# 3_3VTo5V.net
KiCad netlist of a schematic drawn in Altium Designer
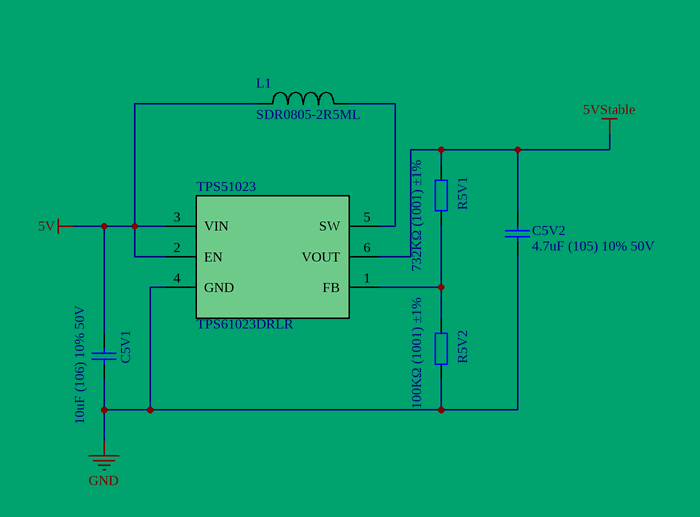
[diagram p0: 3.3VTo5V.SchDoc]

(export (version "E")
  (design (tool "Eeschema 10.0.6"))
  (components
    (comp (ref "C5V1")
      (value "10uF (106) 10% 50V")
      (footprint "1206_C")
      (description "贴片电容")
      (libsource (lib "AD封装2018.9.19Miscellaneous Devices LC") (part "1206 10uF (106) 10% 50V"))
    )
    (comp (ref "C5V2")
      (value "4.7uF (105) 10% 50V")
      (footprint "1206_C")
      (description "贴片电容")
      (libsource (lib "AD封装2018.9.19Miscellaneous Devices LC") (part "1206 1uF (105) 10% 50V"))
    )
    (comp (ref "L1")
      (value "SDR0805-2R5ML")
      (footprint "SDR0805")
      (description "Imported")
      (libsource (lib "ExportLIBCompile") (part "SDR0805-2R5ML"))
    )
    (comp (ref "R5V1")
      (value "732KΩ (1001) ±1%")
      (footprint "1206_R")
      (description "贴片电阻")
      (libsource (lib "AD封装2018.9.19Miscellaneous Devices LC") (part "1206 1KΩ (1001) 1%"))
    )
    (comp (ref "R5V2")
      (value "100KΩ (1001) ±1%")
      (footprint "1206_R")
      (description "贴片电阻")
      (libsource (lib "AD封装2018.9.19Miscellaneous Devices LC") (part "1206 1KΩ (1001) 1%"))
    )
    (comp (ref "TPS51023")
      (value "TPS61023DRLR")
      (footprint "DRL0006A")
      (description "Imported")
      (fields (field (name "MANUFACTURER") "Texas Instruments") (field (name "PARTNUMBER") "TPS61023DRL"))
      (libsource (lib "ExportLIBCompile") (part "TPS61023DRLR"))
    )
  )
  (nets
    (net (code "1") (name "5V") (class "Default")
      (node (ref "C5V1") (pin "2") (pinfunction "2_2") (pintype "passive"))
      (node (ref "L1") (pin "1") (pinfunction "1_1") (pintype "passive"))
      (node (ref "TPS51023") (pin "2") (pinfunction "EN_2") (pintype "passive"))
      (node (ref "TPS51023") (pin "3") (pinfunction "VIN_3") (pintype "power_in"))
    )
    (net (code "2") (name "5VStable") (class "Default")
      (node (ref "C5V2") (pin "2") (pinfunction "2_2") (pintype "passive"))
      (node (ref "R5V1") (pin "2") (pinfunction "2_2") (pintype "passive"))
      (node (ref "TPS51023") (pin "6") (pinfunction "VOUT_6") (pintype "power_in"))
    )
    (net (code "3") (name "GND") (class "Default")
      (node (ref "C5V1") (pin "1") (pinfunction "1_1") (pintype "passive"))
      (node (ref "C5V2") (pin "1") (pinfunction "1_1") (pintype "passive"))
      (node (ref "R5V2") (pin "1") (pinfunction "1_1") (pintype "passive"))
      (node (ref "TPS51023") (pin "4") (pinfunction "GND_4") (pintype "power_in"))
    )
    (net (code "4") (name "Net-(TPS51023-FB)") (class "Default")
      (node (ref "R5V1") (pin "1") (pinfunction "1_1") (pintype "passive"))
      (node (ref "R5V2") (pin "2") (pinfunction "2_2") (pintype "passive"))
      (node (ref "TPS51023") (pin "1") (pinfunction "FB_1") (pintype "passive"))
    )
    (net (code "5") (name "Net-(TPS51023-SW)") (class "Default")
      (node (ref "L1") (pin "2") (pinfunction "2_2") (pintype "passive"))
      (node (ref "TPS51023") (pin "5") (pinfunction "SW_5") (pintype "power_in"))
    )
  )
)
